# XLR_IN_board_2026-02-06.net
KiCad netlist of a schematic drawn in EasyEDA Pro
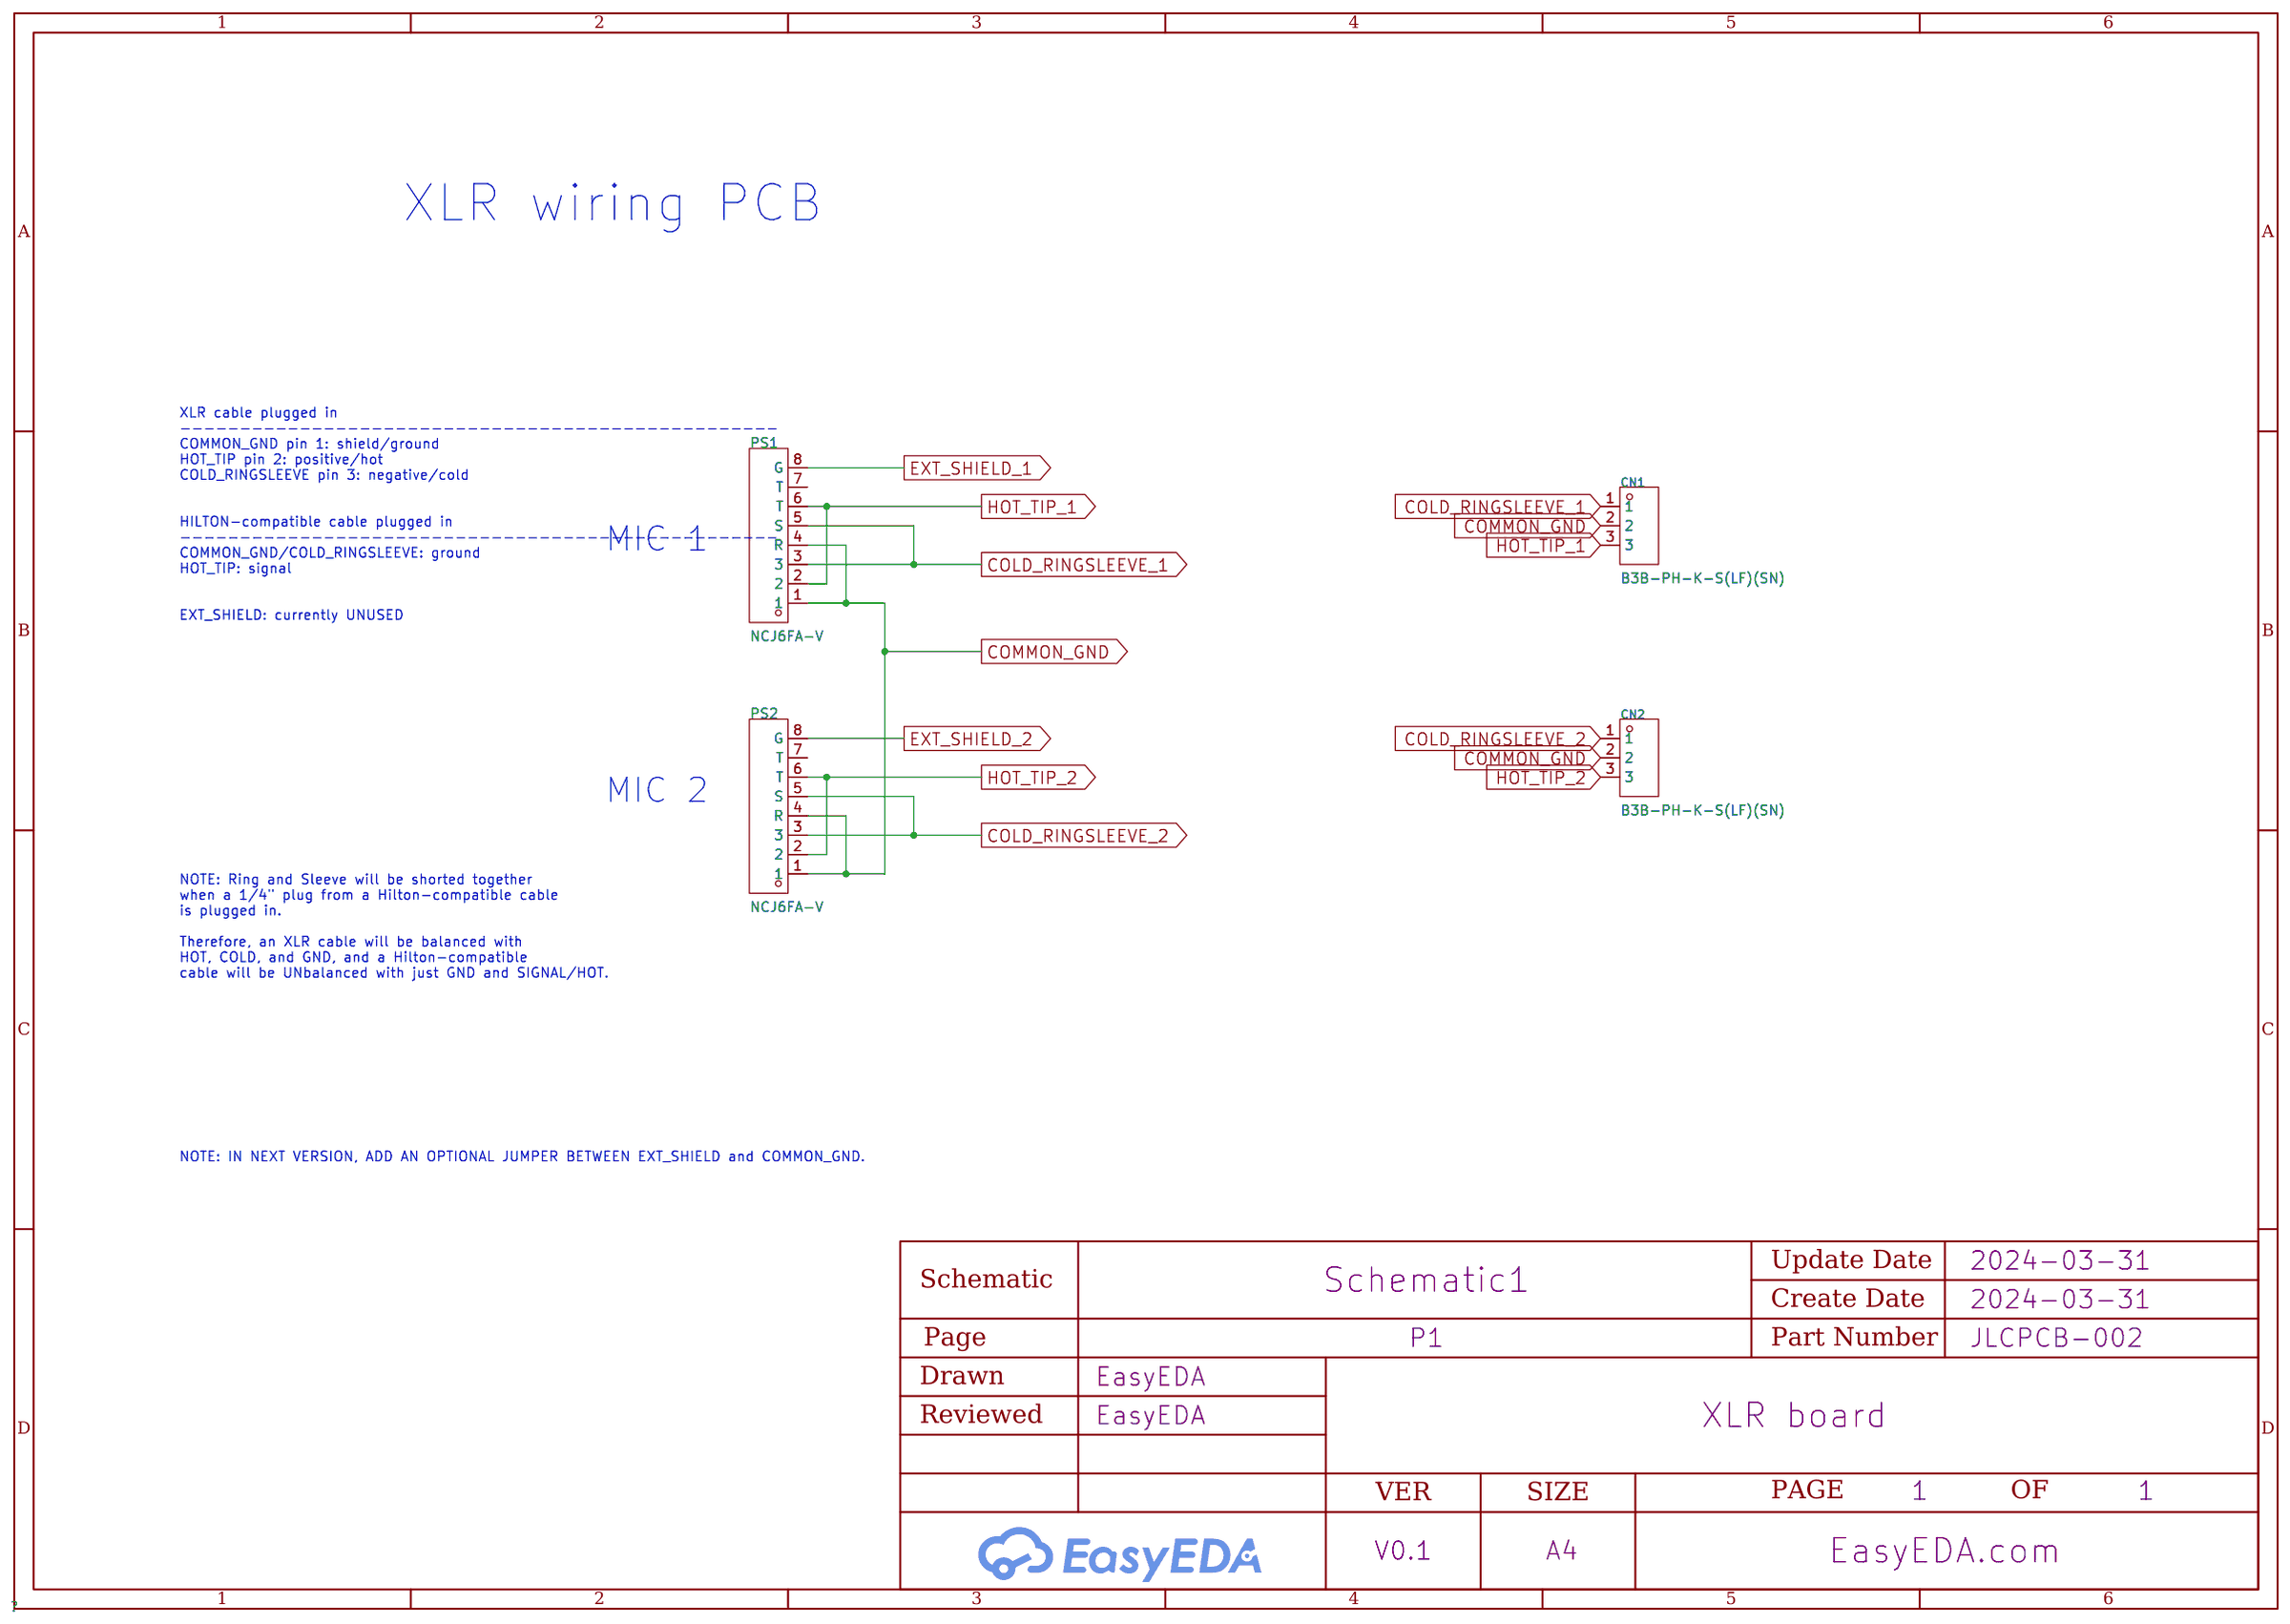
[diagram p0: schematic sheet]

(export (version "E")
  (design (tool "Eeschema 10.0.6"))
  (components
    (comp (ref "CN1")
      (value "B3B-PH-K-S(LF)(SN)")
      (footprint "easyedapro:CONN-TH_B3B-PH-K-S")
      (fields (field (name "Manufacturer") "JST"))
      (libsource (lib "easyedapro") (part "B3B-PH-K-S(LF)(SN)"))
    )
    (comp (ref "CN2")
      (value "B3B-PH-K-S(LF)(SN)")
      (footprint "easyedapro:CONN-TH_B3B-PH-K-S")
      (fields (field (name "Manufacturer") "JST"))
      (libsource (lib "easyedapro") (part "B3B-PH-K-S(LF)(SN)"))
    )
    (comp (ref "PS1")
      (value "NCJ6FA-V")
      (footprint "easyedapro:CONN-TH_NCJ6FA-V")
      (fields (field (name "Manufacturer") "NEUTRIK(优曲克)"))
      (libsource (lib "easyedapro") (part "NCJ6FA-V"))
    )
    (comp (ref "PS2")
      (value "NCJ6FA-V")
      (footprint "easyedapro:CONN-TH_NCJ6FA-V")
      (fields (field (name "Manufacturer") "NEUTRIK(优曲克)"))
      (libsource (lib "easyedapro") (part "NCJ6FA-V"))
    )
  )
  (nets
    (net (code "1") (name "COLD_RINGSLEEVE_1") (class "Default")
      (node (ref "CN1") (pin "1") (pinfunction "1_1") (pintype "input"))
      (node (ref "PS1") (pin "3") (pinfunction "3_3") (pintype "input"))
      (node (ref "PS1") (pin "5") (pinfunction "S_5") (pintype "input"))
    )
    (net (code "2") (name "COLD_RINGSLEEVE_2") (class "Default")
      (node (ref "CN2") (pin "1") (pinfunction "1_1") (pintype "input"))
      (node (ref "PS2") (pin "3") (pinfunction "3_3") (pintype "input"))
      (node (ref "PS2") (pin "5") (pinfunction "S_5") (pintype "input"))
    )
    (net (code "3") (name "COMMON_GND") (class "Default")
      (node (ref "CN1") (pin "2") (pinfunction "2_2") (pintype "input"))
      (node (ref "CN2") (pin "2") (pinfunction "2_2") (pintype "input"))
      (node (ref "PS1") (pin "1") (pinfunction "1_1") (pintype "input"))
      (node (ref "PS1") (pin "4") (pinfunction "R_4") (pintype "input"))
      (node (ref "PS2") (pin "1") (pinfunction "1_1") (pintype "input"))
      (node (ref "PS2") (pin "4") (pinfunction "R_4") (pintype "input"))
    )
    (net (code "4") (name "EXT_SHIELD_1") (class "Default")
      (node (ref "PS1") (pin "8") (pinfunction "G_8") (pintype "input"))
    )
    (net (code "5") (name "EXT_SHIELD_2") (class "Default")
      (node (ref "PS2") (pin "8") (pinfunction "G_8") (pintype "input"))
    )
    (net (code "6") (name "HOT_TIP_1") (class "Default")
      (node (ref "CN1") (pin "3") (pinfunction "3_3") (pintype "input"))
      (node (ref "PS1") (pin "2") (pinfunction "2_2") (pintype "input"))
      (node (ref "PS1") (pin "6") (pinfunction "T_6") (pintype "input"))
    )
    (net (code "7") (name "HOT_TIP_2") (class "Default")
      (node (ref "CN2") (pin "3") (pinfunction "3_3") (pintype "input"))
      (node (ref "PS2") (pin "2") (pinfunction "2_2") (pintype "input"))
      (node (ref "PS2") (pin "6") (pinfunction "T_6") (pintype "input"))
    )
    (net (code "8") (name "unconnected-(PS1-T-Pad7)") (class "Default")
      (node (ref "PS1") (pin "7") (pinfunction "T_7") (pintype "input"))
    )
    (net (code "9") (name "unconnected-(PS2-T-Pad7)") (class "Default")
      (node (ref "PS2") (pin "7") (pinfunction "T_7") (pintype "input"))
    )
  )
)
